# USBPower.net
KiCad netlist of a schematic drawn in EAGLE
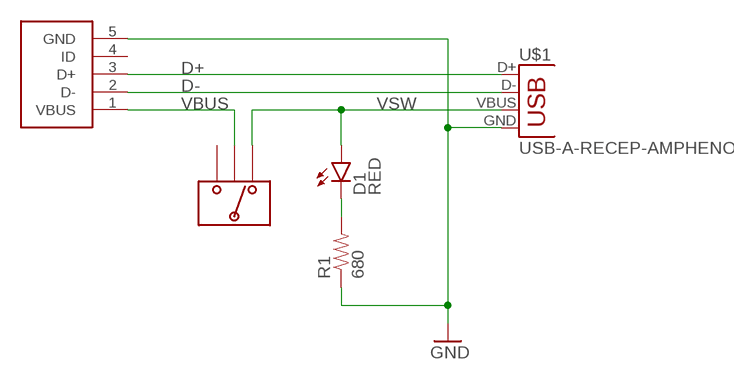
[diagram p0: schematic, sheet 1]

(export (version "E")
  (design (tool "Eeschema 10.0.6"))
  (components
    (comp (ref "D1")
      (value "RED")
      (footprint "eagle-import:LED-0603")
      (libsource (lib "eagle-import") (part "LED-RED"))
    )
    (comp (ref "R1")
      (value "680")
      (footprint "eagle-import:0805")
      (libsource (lib "eagle-import") (part "RES-680-0805"))
    )
    (comp (ref "U$1")
      (value "USB-A-RECEP-AMPHENOL")
      (footprint "eagle-import:USB-A-RECEP-AMPHENOL")
      (libsource (lib "eagle-import") (part "USB-A-RECEP-AMPHENOL"))
    )
    (comp (ref "U$2")
      (value "USB-MICRO-B-SOCKET-AMPHENOL")
      (footprint "eagle-import:USB-B-SMT-AMPHENOL")
      (libsource (lib "eagle-import") (part "USB-MICRO-B-SOCKET-AMPHENOL"))
    )
    (comp (ref "U$3")
      (value "SWITCH-SLIDE-SPDT-TH")
      (footprint "eagle-import:SWITCH-SLIDE-SPDT-TH")
      (libsource (lib "eagle-import") (part "SWITCH-SLIDE-SPDT-TH"))
    )
  )
  (nets
    (net (code "1") (name "/D+") (class "Default")
      (node (ref "U$1") (pin "D+") (pinfunction "D+_D+") (pintype "bidirectional"))
      (node (ref "U$2") (pin "3") (pinfunction "D+_3") (pintype "passive"))
    )
    (net (code "2") (name "/D-") (class "Default")
      (node (ref "U$1") (pin "D-") (pinfunction "D-_D-") (pintype "bidirectional"))
      (node (ref "U$2") (pin "2") (pinfunction "D-_2") (pintype "passive"))
    )
    (net (code "3") (name "/VBUS") (class "Default")
      (node (ref "U$2") (pin "1") (pinfunction "VBUS_1") (pintype "passive"))
      (node (ref "U$3") (pin "2") (pinfunction "2_2") (pintype "passive"))
    )
    (net (code "4") (name "/VSW") (class "Default")
      (node (ref "D1") (pin "A") (pinfunction "A_A") (pintype "passive"))
      (node (ref "U$1") (pin "VBUS") (pinfunction "VBUS_VBUS") (pintype "bidirectional"))
      (node (ref "U$3") (pin "1") (pinfunction "1_1") (pintype "passive"))
    )
    (net (code "5") (name "GND") (class "Default")
      (node (ref "R1") (pin "1") (pinfunction "1_1") (pintype "passive"))
      (node (ref "U$1") (pin "GND") (pinfunction "GND_GND") (pintype "bidirectional"))
      (node (ref "U$2") (pin "5") (pinfunction "GND_5") (pintype "passive"))
    )
    (net (code "6") (name "Net-(D1-PadC)") (class "Default")
      (node (ref "D1") (pin "C") (pinfunction "C_C") (pintype "passive"))
      (node (ref "R1") (pin "2") (pinfunction "2_2") (pintype "passive"))
    )
    (net (code "7") (name "unconnected-(U$2-ID-Pad4)") (class "Default")
      (node (ref "U$2") (pin "4") (pinfunction "ID_4") (pintype "passive"))
    )
    (net (code "8") (name "unconnected-(U$3-Pad3)") (class "Default")
      (node (ref "U$3") (pin "3") (pinfunction "3_3") (pintype "passive"))
    )
  )
)
